# FOC_DRV8323.net
KiCad netlist of a schematic drawn in Altium Designer
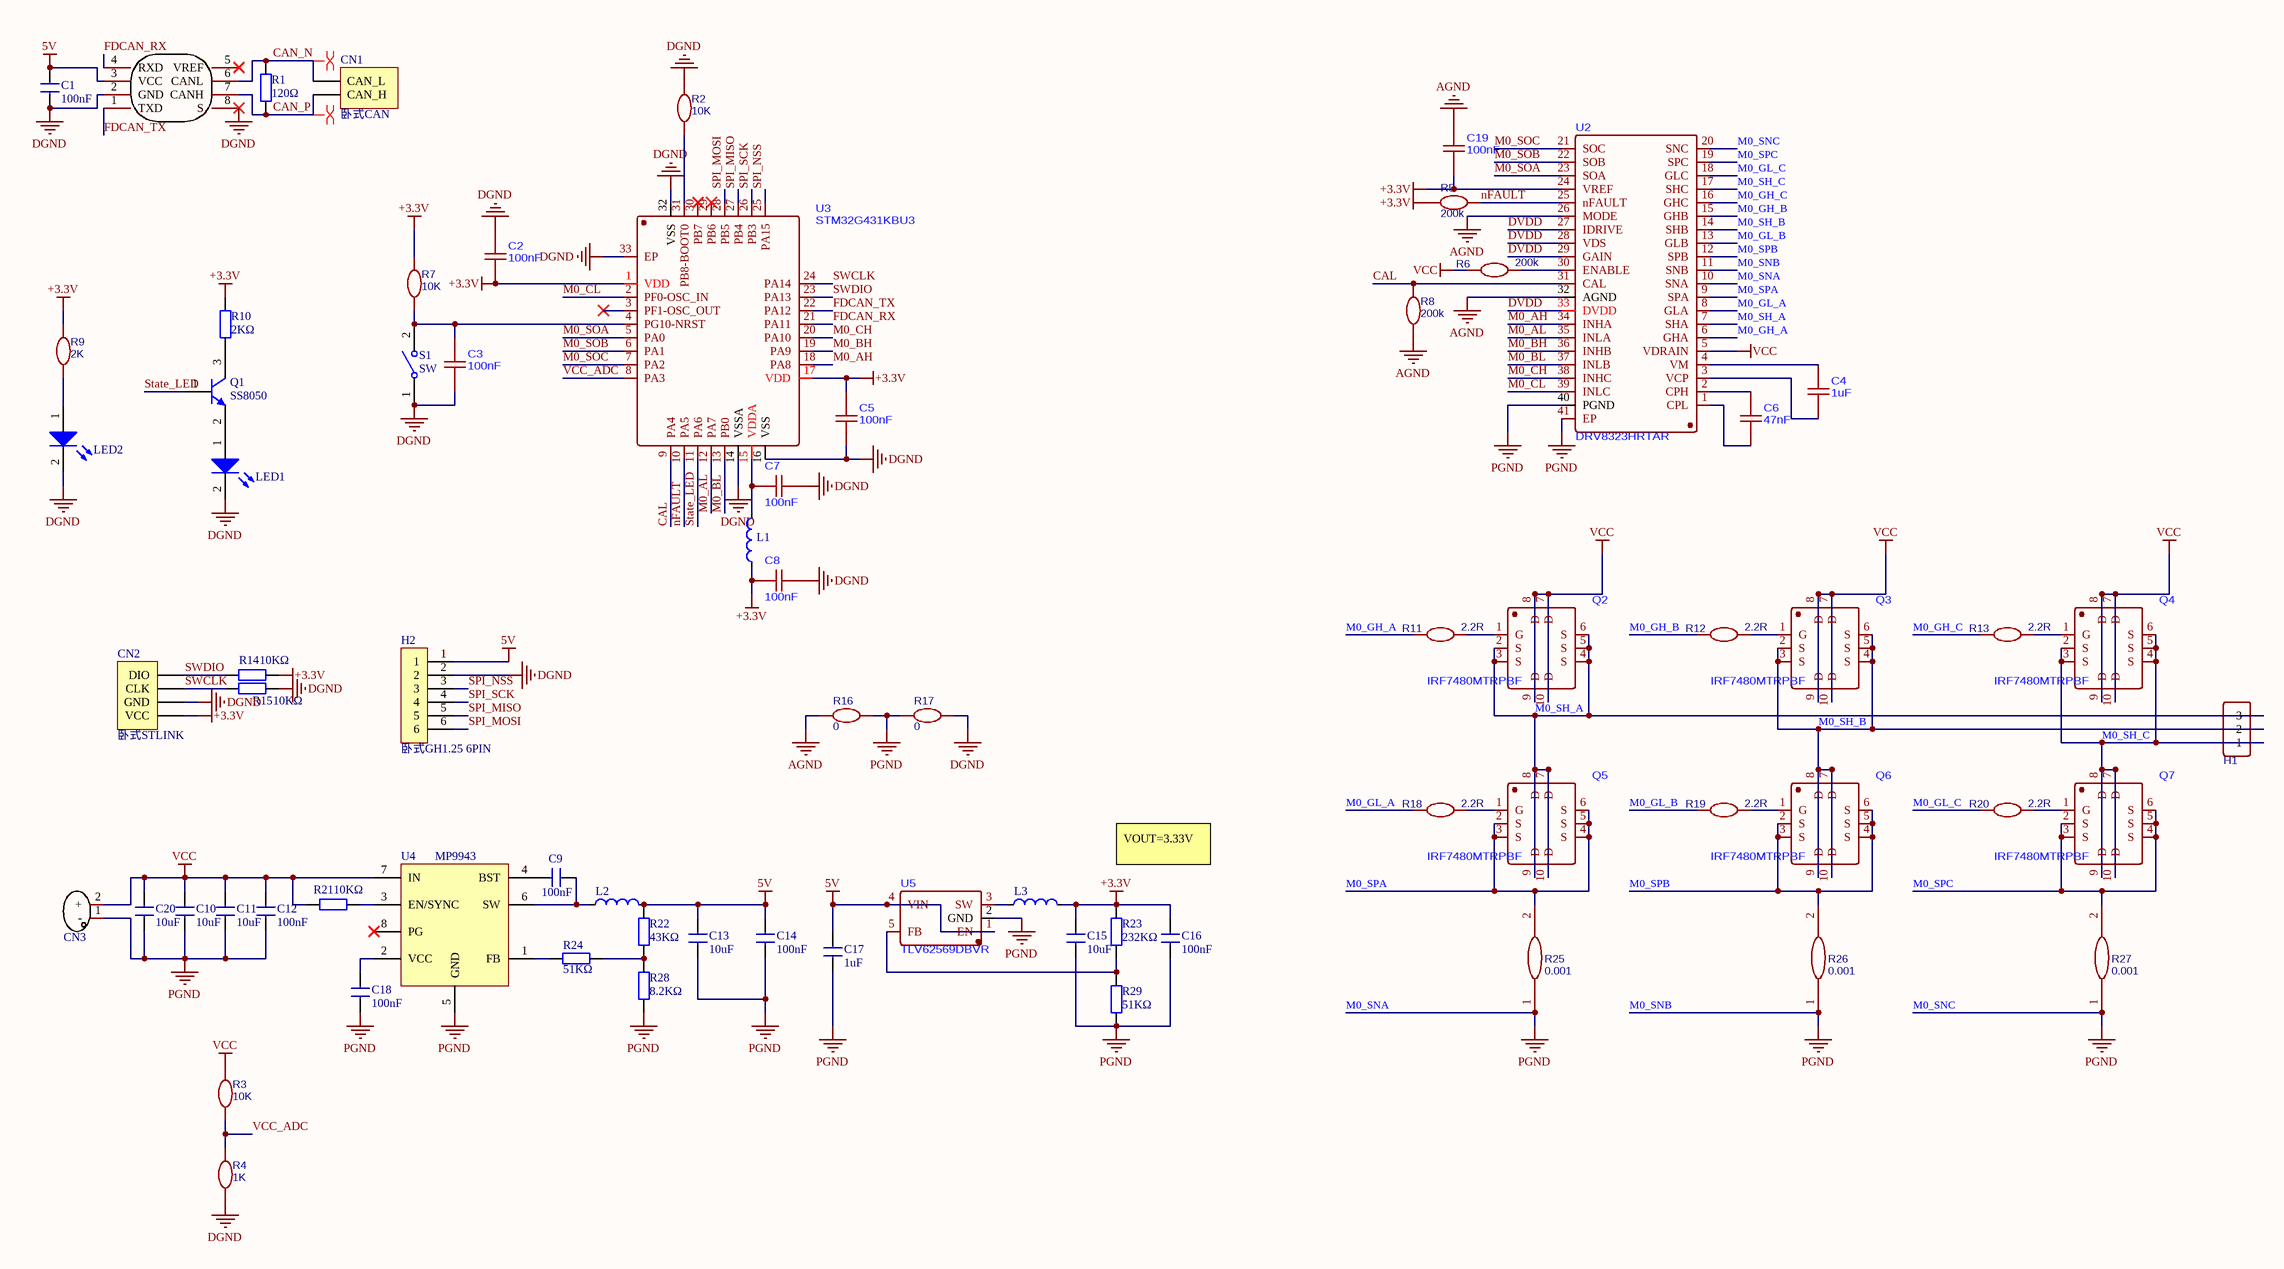
[diagram p0: FOC_DRV8323.SchDoc]

(export (version "E")
  (design (tool "Eeschema 10.0.6"))
  (components
    (comp (ref "C1")
      (value "100nF")
      (footprint "c0402")
      (description "贴片电容0402")
      (libsource (lib "Integrated_Library1") (part "0402贴片电容"))
    )
    (comp (ref "C2") (value "100nF") (footprint "c0402") (libsource (lib "PETO") (part "CC0201JRX7R9BB101")))
    (comp (ref "C3") (value "100nF") (footprint "c0402") (libsource (lib "PETO") (part "CC0201JRX7R9BB101")))
    (comp (ref "C4") (value "1uF") (footprint "c0402") (libsource (lib "PETO") (part "CC0201JRX7R9BB101")))
    (comp (ref "C5") (value "100nF") (footprint "c0402") (libsource (lib "PETO") (part "CC0201JRX7R9BB101")))
    (comp (ref "C6") (value "47nF") (footprint "c0402") (libsource (lib "PETO") (part "CC0201JRX7R9BB101")))
    (comp (ref "C7") (value "100nF") (footprint "c0402") (libsource (lib "PETO") (part "CC0201JRX7R9BB101")))
    (comp (ref "C8") (value "100nF") (footprint "c0402") (libsource (lib "PETO") (part "CC0201JRX7R9BB101")))
    (comp (ref "C9")
      (value "100nF")
      (footprint "c0402")
      (description "贴片电容0402")
      (libsource (lib "Integrated_Library1") (part "0402贴片电容"))
    )
    (comp (ref "C10")
      (value "10uF")
      (footprint "1210")
      (description "1210贴片电容")
      (libsource (lib "Integrated_Library1") (part "1210贴片电容"))
    )
    (comp (ref "C11")
      (value "10uF")
      (footprint "1210")
      (description "1210贴片电容")
      (libsource (lib "Integrated_Library1") (part "1210贴片电容"))
    )
    (comp (ref "C12")
      (value "100nF")
      (footprint "c0402")
      (description "贴片电容0402")
      (libsource (lib "Integrated_Library1") (part "0402贴片电容"))
    )
    (comp (ref "C13")
      (value "10uF")
      (footprint "1210")
      (description "1210贴片电容")
      (libsource (lib "Integrated_Library1") (part "1210贴片电容"))
    )
    (comp (ref "C14")
      (value "100nF")
      (footprint "c0402")
      (description "贴片电容0402")
      (libsource (lib "Integrated_Library1") (part "0402贴片电容"))
    )
    (comp (ref "C15")
      (value "10uF")
      (footprint "1210")
      (description "贴片电容0402")
      (libsource (lib "Integrated_Library1") (part "0402贴片电容"))
    )
    (comp (ref "C16")
      (value "100nF")
      (footprint "c0402")
      (description "贴片电容0402")
      (libsource (lib "Integrated_Library1") (part "0402贴片电容"))
    )
    (comp (ref "C17")
      (value "1uF")
      (footprint "c0402")
      (description "贴片电容0402")
      (libsource (lib "Integrated_Library1") (part "0402贴片电容"))
    )
    (comp (ref "C18")
      (value "100nF")
      (footprint "c0402")
      (description "贴片电容0402")
      (libsource (lib "Integrated_Library1") (part "0402贴片电容"))
    )
    (comp (ref "C19") (value "100nF") (footprint "c0402") (libsource (lib "PETO") (part "CC0201JRX7R9BB101")))
    (comp (ref "C20")
      (value "10uF")
      (footprint "1210")
      (description "1210贴片电容")
      (libsource (lib "Integrated_Library1") (part "1210贴片电容"))
    )
    (comp (ref "CN1")
      (value "卧式CAN")
      (footprint "GH1.25 2P 卧式")
      (fields (field (name "PUBLISHER") "Altium Limited"))
      (libsource (lib "Integrated_Library1") (part "卧式CAN"))
    )
    (comp (ref "CN2")
      (value "卧式STLINK")
      (footprint "CONN-SMD_4P-P1.25_GH1.25-4P")
      (libsource (lib "Integrated_Library1") (part "卧式STLINK"))
    )
    (comp (ref "CN3") (value "XT30_1") (footprint "XT30卧式焊盘") (libsource (lib "Schlib1") (part "XT30_1")))
    (comp (ref "H1")
      (value "MR30-M")
      (footprint "MR30")
      (fields (field (name "BOM_SUPPLIER PART") "C99873") (field (name "CONTRIBUTOR") "LCEDA_Lib"))
      (libsource (lib "altium-import") (part "root_2_MR30-M_"))
    )
    (comp (ref "H2")
      (value "卧式GH1.25 6PIN")
      (footprint "CONN-SMD_6P-P1.25_XYECONN_XY-GH1.25-6A61")
      (libsource (lib "En") (part "卧式GH1.25 6PIN"))
    )
    (comp (ref "L1")
      (value "1008屏蔽电感")
      (footprint "R0603")
      (libsource (lib "Integrated_Library1") (part "1008屏蔽电感"))
    )
    (comp (ref "L2")
      (value "1008屏蔽电感")
      (footprint "IND-SMD_L2.5-W2.0")
      (libsource (lib "Integrated_Library1") (part "1008屏蔽电感"))
    )
    (comp (ref "L3")
      (value "1008屏蔽电感")
      (footprint "IND-SMD_L2.5-W2.0")
      (libsource (lib "Integrated_Library1") (part "1008屏蔽电感"))
    )
    (comp (ref "LED1")
      (value "LED")
      (footprint "led0805")
      (description "0805贴片LED")
      (libsource (lib "Integrated_Library1") (part "0805贴片LED"))
    )
    (comp (ref "LED2")
      (value "LED")
      (footprint "led0805")
      (description "0805贴片LED")
      (libsource (lib "Integrated_Library1") (part "0805贴片LED"))
    )
    (comp (ref "Q1")
      (value "SS8050")
      (footprint "SOT-23-3_L2.9-W1.3-P1.90-LS2.4-BR")
      (description "三极管")
      (libsource (lib "Integrated_Library1") (part "2N2222"))
    )
    (comp (ref "Q2")
      (value "IRF7480MTRPBF")
      (footprint "TRS-SMD_IRF7480MTRPBF")
      (libsource (lib "FOC_DRV8301") (part "IRF7480MTRPBF"))
    )
    (comp (ref "Q3")
      (value "IRF7480MTRPBF")
      (footprint "TRS-SMD_IRF7480MTRPBF")
      (libsource (lib "FOC_DRV8301") (part "IRF7480MTRPBF"))
    )
    (comp (ref "Q4")
      (value "IRF7480MTRPBF")
      (footprint "TRS-SMD_IRF7480MTRPBF")
      (libsource (lib "FOC_DRV8301") (part "IRF7480MTRPBF"))
    )
    (comp (ref "Q5")
      (value "IRF7480MTRPBF")
      (footprint "TRS-SMD_IRF7480MTRPBF")
      (libsource (lib "FOC_DRV8301") (part "IRF7480MTRPBF"))
    )
    (comp (ref "Q6")
      (value "IRF7480MTRPBF")
      (footprint "TRS-SMD_IRF7480MTRPBF")
      (libsource (lib "FOC_DRV8301") (part "IRF7480MTRPBF"))
    )
    (comp (ref "Q7")
      (value "IRF7480MTRPBF")
      (footprint "TRS-SMD_IRF7480MTRPBF")
      (libsource (lib "FOC_DRV8301") (part "IRF7480MTRPBF"))
    )
    (comp (ref "R1")
      (value "120Ω")
      (footprint "R0402")
      (description "0402贴片电阻")
      (libsource (lib "") (part "0402贴片电阻_4"))
    )
    (comp (ref "R2")
      (value "10K")
      (footprint "R0402")
      (fields
        (field (name "BOM_MANUFACTURER PART") "0603WAJ022JT5E")
        (field (name "BOM_SUPPLIER PART") "C25226")
      )
      (libsource (lib "altium-import") (part "root_3_2.2R_"))
    )
    (comp (ref "R3")
      (value "10K")
      (footprint "R0402")
      (fields
        (field (name "BOM_MANUFACTURER PART") "0603WAJ022JT5E")
        (field (name "BOM_SUPPLIER PART") "C25226")
      )
      (libsource (lib "altium-import") (part "root_1_2.2R_"))
    )
    (comp (ref "R4")
      (value "1K")
      (footprint "R0402")
      (fields
        (field (name "BOM_MANUFACTURER PART") "0603WAJ022JT5E")
        (field (name "BOM_SUPPLIER PART") "C25226")
      )
      (libsource (lib "altium-import") (part "root_1_2.2R_"))
    )
    (comp (ref "R5")
      (value "200k")
      (footprint "R0402")
      (fields
        (field (name "BOM_MANUFACTURER PART") "0603WAJ022JT5E")
        (field (name "BOM_SUPPLIER PART") "C25226")
      )
      (libsource (lib "altium-import") (part "root_0_2.2R_"))
    )
    (comp (ref "R6")
      (value "200k")
      (footprint "R0402")
      (fields
        (field (name "BOM_MANUFACTURER PART") "0603WAJ022JT5E")
        (field (name "BOM_SUPPLIER PART") "C25226")
      )
      (libsource (lib "altium-import") (part "root_2_2.2R_"))
    )
    (comp (ref "R7")
      (value "10K")
      (footprint "R0402")
      (fields
        (field (name "BOM_MANUFACTURER PART") "0603WAJ022JT5E")
        (field (name "BOM_SUPPLIER PART") "C25226")
      )
      (libsource (lib "altium-import") (part "root_3_2.2R_"))
    )
    (comp (ref "R8")
      (value "200k")
      (footprint "R0402")
      (fields
        (field (name "BOM_MANUFACTURER PART") "0603WAJ022JT5E")
        (field (name "BOM_SUPPLIER PART") "C25226")
      )
      (libsource (lib "altium-import") (part "root_3_2.2R_"))
    )
    (comp (ref "R9")
      (value "2K")
      (footprint "R0402")
      (fields
        (field (name "BOM_MANUFACTURER PART") "0603WAJ022JT5E")
        (field (name "BOM_SUPPLIER PART") "C25226")
      )
      (libsource (lib "altium-import") (part "root_3_2.2R_"))
    )
    (comp (ref "R10")
      (value "2KΩ")
      (footprint "R0402")
      (description "0402贴片电阻")
      (libsource (lib "") (part "0402贴片电阻_4"))
    )
    (comp (ref "R11")
      (value "2.2R")
      (footprint "R0402")
      (fields
        (field (name "BOM_MANUFACTURER PART") "0603WAJ022JT5E")
        (field (name "BOM_SUPPLIER PART") "C25226")
      )
      (libsource (lib "altium-import") (part "root_2_2.2R_"))
    )
    (comp (ref "R12")
      (value "2.2R")
      (footprint "R0402")
      (fields
        (field (name "BOM_MANUFACTURER PART") "0603WAJ022JT5E")
        (field (name "BOM_SUPPLIER PART") "C25226")
      )
      (libsource (lib "altium-import") (part "root_2_2.2R_"))
    )
    (comp (ref "R13")
      (value "2.2R")
      (footprint "R0402")
      (fields
        (field (name "BOM_MANUFACTURER PART") "0603WAJ022JT5E")
        (field (name "BOM_SUPPLIER PART") "C25226")
      )
      (libsource (lib "altium-import") (part "root_2_2.2R_"))
    )
    (comp (ref "R14")
      (value "10KΩ")
      (footprint "R0402")
      (description "0402贴片电阻")
      (libsource (lib "Integrated_Library1") (part "0402贴片电阻"))
    )
    (comp (ref "R15")
      (value "10KΩ")
      (footprint "R0402")
      (description "0402贴片电阻")
      (libsource (lib "") (part "0402贴片电阻_3"))
    )
    (comp (ref "R16")
      (value "0")
      (footprint "R0402")
      (fields
        (field (name "BOM_MANUFACTURER PART") "0603WAJ022JT5E")
        (field (name "BOM_SUPPLIER PART") "C25226")
      )
      (libsource (lib "altium-import") (part "root_0_2.2R_"))
    )
    (comp (ref "R17")
      (value "0")
      (footprint "R0402")
      (fields
        (field (name "BOM_MANUFACTURER PART") "0603WAJ022JT5E")
        (field (name "BOM_SUPPLIER PART") "C25226")
      )
      (libsource (lib "altium-import") (part "root_0_2.2R_"))
    )
    (comp (ref "R18")
      (value "2.2R")
      (footprint "R0402")
      (fields
        (field (name "BOM_MANUFACTURER PART") "0603WAJ022JT5E")
        (field (name "BOM_SUPPLIER PART") "C25226")
      )
      (libsource (lib "altium-import") (part "root_2_2.2R_"))
    )
    (comp (ref "R19")
      (value "2.2R")
      (footprint "R0402")
      (fields
        (field (name "BOM_MANUFACTURER PART") "0603WAJ022JT5E")
        (field (name "BOM_SUPPLIER PART") "C25226")
      )
      (libsource (lib "altium-import") (part "root_2_2.2R_"))
    )
    (comp (ref "R20")
      (value "2.2R")
      (footprint "R0402")
      (fields
        (field (name "BOM_MANUFACTURER PART") "0603WAJ022JT5E")
        (field (name "BOM_SUPPLIER PART") "C25226")
      )
      (libsource (lib "altium-import") (part "root_2_2.2R_"))
    )
    (comp (ref "R21")
      (value "10KΩ")
      (footprint "R0402")
      (description "0402贴片电阻")
      (libsource (lib "") (part "0402贴片电阻_1"))
    )
    (comp (ref "R22")
      (value "43KΩ")
      (footprint "R0402")
      (description "0402贴片电阻")
      (libsource (lib "") (part "0402贴片电阻_2"))
    )
    (comp (ref "R23")
      (value "232KΩ")
      (footprint "R0402")
      (description "0402贴片电阻")
      (libsource (lib "") (part "0402贴片电阻_2"))
    )
    (comp (ref "R24")
      (value "51KΩ")
      (footprint "R0402")
      (description "0402贴片电阻")
      (libsource (lib "") (part "0402贴片电阻_1"))
    )
    (comp (ref "R25")
      (value "0.001")
      (footprint "R0612")
      (fields
        (field (name "BOM_SUPPLIER PART") "C2681067")
        (field (name "BOM_MANUFACTURER PART") "LR2512-23R0005J4")
        (field (name "CONTRIBUTOR") "LCSC")
      )
      (libsource (lib "altium-import") (part "root_1_0.0005_"))
    )
    (comp (ref "R26")
      (value "0.001")
      (footprint "R0612")
      (fields
        (field (name "BOM_SUPPLIER PART") "C2681067")
        (field (name "BOM_MANUFACTURER PART") "LR2512-23R0005J4")
        (field (name "CONTRIBUTOR") "LCSC")
      )
      (libsource (lib "altium-import") (part "root_1_0.0005_"))
    )
    (comp (ref "R27")
      (value "0.001")
      (footprint "R0612")
      (fields
        (field (name "BOM_SUPPLIER PART") "C2681067")
        (field (name "BOM_MANUFACTURER PART") "LR2512-23R0005J4")
        (field (name "CONTRIBUTOR") "LCSC")
      )
      (libsource (lib "altium-import") (part "root_1_0.0005_"))
    )
    (comp (ref "R28")
      (value "8.2KΩ")
      (footprint "R0402")
      (description "0402贴片电阻")
      (libsource (lib "") (part "0402贴片电阻_2"))
    )
    (comp (ref "R29")
      (value "51KΩ")
      (footprint "R0402")
      (description "0402贴片电阻")
      (libsource (lib "") (part "0402贴片电阻_2"))
    )
    (comp (ref "S1")
      (value "SW")
      (footprint "KEY_SMD")
      (description "开关")
      (libsource (lib "Integrated_Library1") (part "SW"))
    )
    (comp (ref "U1")
      (value "SN65HVD1050DR")
      (footprint "SOIC-8_L4.9-W3.9-P1.27-LS6.0-BL")
      (description "CAN芯片")
      (fields (field (name "MANUFACTURER") "TI(德州仪器)"))
      (libsource (lib "Integrated_Library1") (part "SN65HVD1050DR"))
    )
    (comp (ref "U2")
      (value "DRV8323HRTAR")
      (footprint "QFN-40_L6.0-W6.0-P0.50-BL-EP4.5")
      (libsource (lib "FOC_DRV8323") (part "DRV8323HRTAR"))
    )
    (comp (ref "U3")
      (value "STM32G431KBU3")
      (footprint "UFQFPN-32_L5.0-W5.0-P0.50-BL-EP3.5")
      (libsource (lib "FOC_DRV8323") (part "STM32G431KBU3"))
    )
    (comp (ref "U4")
      (value "MP9943")
      (footprint "QFN-8 3x3")
      (libsource (lib "Integrated_Library1") (part "MP9943"))
    )
    (comp (ref "U5")
      (value "TLV62569DBVR")
      (footprint "SOT-23-5_L3.0-W1.7-P0.95-LS2.8-BR")
      (libsource (lib "FOC_DRV8323") (part "TLV62569DBVR"))
    )
  )
  (nets
    (net (code "1") (name "+3.3V") (class "Default")
      (node (ref "C15") (pin "2") (pinfunction "2_2") (pintype "passive"))
      (node (ref "C16") (pin "2") (pinfunction "2_2") (pintype "passive"))
      (node (ref "C19") (pin "1") (pinfunction "1_1") (pintype "passive"))
      (node (ref "C2") (pin "2") (pinfunction "2_2") (pintype "passive"))
      (node (ref "C5") (pin "2") (pinfunction "2_2") (pintype "passive"))
      (node (ref "C8") (pin "2") (pinfunction "2_2") (pintype "passive"))
      (node (ref "CN2") (pin "1") (pinfunction "VCC_1") (pintype "passive"))
      (node (ref "L1") (pin "1") (pinfunction "1_1") (pintype "passive"))
      (node (ref "L3") (pin "2") (pinfunction "2_2") (pintype "passive"))
      (node (ref "R10") (pin "2") (pinfunction "2_2") (pintype "passive"))
      (node (ref "R14") (pin "1") (pinfunction "1_1") (pintype "passive"))
      (node (ref "R23") (pin "2") (pinfunction "2_2") (pintype "passive"))
      (node (ref "R5") (pin "1") (pinfunction "1_1") (pintype "passive"))
      (node (ref "R7") (pin "1") (pinfunction "1_1") (pintype "passive"))
      (node (ref "R9") (pin "1") (pinfunction "1_1") (pintype "passive"))
      (node (ref "U2") (pin "24") (pinfunction "VREF_24") (pintype "passive"))
      (node (ref "U3") (pin "1") (pinfunction "VDD_1") (pintype "passive"))
      (node (ref "U3") (pin "17") (pinfunction "VDD_17") (pintype "passive"))
    )
    (net (code "2") (name "/CAL") (class "Default")
      (node (ref "R8") (pin "1") (pinfunction "1_1") (pintype "passive"))
      (node (ref "U2") (pin "31") (pinfunction "CAL_31") (pintype "passive"))
      (node (ref "U3") (pin "9") (pinfunction "PA4_9") (pintype "passive"))
    )
    (net (code "3") (name "/CAN_N") (class "Default")
      (node (ref "CN1") (pin "2") (pinfunction "CAN_L_2") (pintype "passive"))
      (node (ref "R1") (pin "2") (pinfunction "2_2") (pintype "passive"))
      (node (ref "U1") (pin "6") (pinfunction "CANL_6") (pintype "passive"))
    )
    (net (code "4") (name "/CAN_P") (class "Default")
      (node (ref "CN1") (pin "1") (pinfunction "CAN_H_1") (pintype "passive"))
      (node (ref "R1") (pin "1") (pinfunction "1_1") (pintype "passive"))
      (node (ref "U1") (pin "7") (pinfunction "CANH_7") (pintype "passive"))
    )
    (net (code "5") (name "/DVDD") (class "Default")
      (node (ref "U2") (pin "27") (pinfunction "IDRIVE_27") (pintype "passive"))
      (node (ref "U2") (pin "28") (pinfunction "VDS_28") (pintype "passive"))
      (node (ref "U2") (pin "29") (pinfunction "GAIN_29") (pintype "passive"))
      (node (ref "U2") (pin "33") (pinfunction "DVDD_33") (pintype "passive"))
    )
    (net (code "6") (name "/FDCAN_RX") (class "Default")
      (node (ref "U1") (pin "4") (pinfunction "RXD_4") (pintype "passive"))
      (node (ref "U3") (pin "21") (pinfunction "PA11_21") (pintype "passive"))
    )
    (net (code "7") (name "/FDCAN_TX") (class "Default")
      (node (ref "U1") (pin "1") (pinfunction "TXD_1") (pintype "passive"))
      (node (ref "U3") (pin "22") (pinfunction "PA12_22") (pintype "passive"))
    )
    (net (code "8") (name "/M0_AH") (class "Default")
      (node (ref "U2") (pin "34") (pinfunction "INHA_34") (pintype "passive"))
      (node (ref "U3") (pin "18") (pinfunction "PA8_18") (pintype "passive"))
    )
    (net (code "9") (name "/M0_AL") (class "Default")
      (node (ref "U2") (pin "35") (pinfunction "INLA_35") (pintype "passive"))
      (node (ref "U3") (pin "12") (pinfunction "PA7_12") (pintype "passive"))
    )
    (net (code "10") (name "/M0_BH") (class "Default")
      (node (ref "U2") (pin "36") (pinfunction "INHB_36") (pintype "passive"))
      (node (ref "U3") (pin "19") (pinfunction "PA9_19") (pintype "passive"))
    )
    (net (code "11") (name "/M0_BL") (class "Default")
      (node (ref "U2") (pin "37") (pinfunction "INLB_37") (pintype "passive"))
      (node (ref "U3") (pin "13") (pinfunction "PB0_13") (pintype "passive"))
    )
    (net (code "12") (name "/M0_CH") (class "Default")
      (node (ref "U2") (pin "38") (pinfunction "INHC_38") (pintype "passive"))
      (node (ref "U3") (pin "20") (pinfunction "PA10_20") (pintype "passive"))
    )
    (net (code "13") (name "/M0_CL") (class "Default")
      (node (ref "U2") (pin "39") (pinfunction "INLC_39") (pintype "passive"))
      (node (ref "U3") (pin "2") (pinfunction "PF0-OSC_IN_2") (pintype "passive"))
    )
    (net (code "14") (name "/M0_GH_A") (class "Default")
      (node (ref "R11") (pin "2") (pinfunction "2_2") (pintype "passive"))
      (node (ref "U2") (pin "6") (pinfunction "GHA_6") (pintype "passive"))
    )
    (net (code "15") (name "/M0_GH_B") (class "Default")
      (node (ref "R12") (pin "2") (pinfunction "2_2") (pintype "passive"))
      (node (ref "U2") (pin "15") (pinfunction "GHB_15") (pintype "passive"))
    )
    (net (code "16") (name "/M0_GH_C") (class "Default")
      (node (ref "R13") (pin "2") (pinfunction "2_2") (pintype "passive"))
      (node (ref "U2") (pin "16") (pinfunction "GHC_16") (pintype "passive"))
    )
    (net (code "17") (name "/M0_GL_A") (class "Default")
      (node (ref "R18") (pin "2") (pinfunction "2_2") (pintype "passive"))
      (node (ref "U2") (pin "8") (pinfunction "GLA_8") (pintype "passive"))
    )
    (net (code "18") (name "/M0_GL_B") (class "Default")
      (node (ref "R19") (pin "2") (pinfunction "2_2") (pintype "passive"))
      (node (ref "U2") (pin "13") (pinfunction "GLB_13") (pintype "passive"))
    )
    (net (code "19") (name "/M0_GL_C") (class "Default")
      (node (ref "R20") (pin "2") (pinfunction "2_2") (pintype "passive"))
      (node (ref "U2") (pin "18") (pinfunction "GLC_18") (pintype "passive"))
    )
    (net (code "20") (name "/M0_SH_A") (class "Default")
      (node (ref "H1") (pin "3") (pinfunction "3_3") (pintype "passive"))
      (node (ref "Q2") (pin "2") (pinfunction "S_2") (pintype "passive"))
      (node (ref "Q2") (pin "3") (pinfunction "S_3") (pintype "passive"))
      (node (ref "Q2") (pin "4") (pinfunction "S_4") (pintype "passive"))
      (node (ref "Q2") (pin "5") (pinfunction "S_5") (pintype "passive"))
      (node (ref "Q2") (pin "6") (pinfunction "S_6") (pintype "passive"))
      (node (ref "Q5") (pin "10") (pinfunction "D_10") (pintype "passive"))
      (node (ref "Q5") (pin "7") (pinfunction "D_7") (pintype "passive"))
      (node (ref "Q5") (pin "8") (pinfunction "D_8") (pintype "passive"))
      (node (ref "Q5") (pin "9") (pinfunction "D_9") (pintype "passive"))
      (node (ref "U2") (pin "7") (pinfunction "SHA_7") (pintype "passive"))
    )
    (net (code "21") (name "/M0_SH_B") (class "Default")
      (node (ref "H1") (pin "2") (pinfunction "2_2") (pintype "passive"))
      (node (ref "Q3") (pin "2") (pinfunction "S_2") (pintype "passive"))
      (node (ref "Q3") (pin "3") (pinfunction "S_3") (pintype "passive"))
      (node (ref "Q3") (pin "4") (pinfunction "S_4") (pintype "passive"))
      (node (ref "Q3") (pin "5") (pinfunction "S_5") (pintype "passive"))
      (node (ref "Q3") (pin "6") (pinfunction "S_6") (pintype "passive"))
      (node (ref "Q6") (pin "10") (pinfunction "D_10") (pintype "passive"))
      (node (ref "Q6") (pin "7") (pinfunction "D_7") (pintype "passive"))
      (node (ref "Q6") (pin "8") (pinfunction "D_8") (pintype "passive"))
      (node (ref "Q6") (pin "9") (pinfunction "D_9") (pintype "passive"))
      (node (ref "U2") (pin "14") (pinfunction "SHB_14") (pintype "passive"))
    )
    (net (code "22") (name "/M0_SH_C") (class "Default")
      (node (ref "H1") (pin "1") (pinfunction "1_1") (pintype "passive"))
      (node (ref "Q4") (pin "2") (pinfunction "S_2") (pintype "passive"))
      (node (ref "Q4") (pin "3") (pinfunction "S_3") (pintype "passive"))
      (node (ref "Q4") (pin "4") (pinfunction "S_4") (pintype "passive"))
      (node (ref "Q4") (pin "5") (pinfunction "S_5") (pintype "passive"))
      (node (ref "Q4") (pin "6") (pinfunction "S_6") (pintype "passive"))
      (node (ref "Q7") (pin "10") (pinfunction "D_10") (pintype "passive"))
      (node (ref "Q7") (pin "7") (pinfunction "D_7") (pintype "passive"))
      (node (ref "Q7") (pin "8") (pinfunction "D_8") (pintype "passive"))
      (node (ref "Q7") (pin "9") (pinfunction "D_9") (pintype "passive"))
      (node (ref "U2") (pin "17") (pinfunction "SHC_17") (pintype "passive"))
    )
    (net (code "23") (name "/M0_SOA") (class "Default")
      (node (ref "U2") (pin "23") (pinfunction "SOA_23") (pintype "passive"))
      (node (ref "U3") (pin "5") (pinfunction "PA0_5") (pintype "passive"))
    )
    (net (code "24") (name "/M0_SOB") (class "Default")
      (node (ref "U2") (pin "22") (pinfunction "SOB_22") (pintype "passive"))
      (node (ref "U3") (pin "6") (pinfunction "PA1_6") (pintype "passive"))
    )
    (net (code "25") (name "/M0_SOC") (class "Default")
      (node (ref "U2") (pin "21") (pinfunction "SOC_21") (pintype "passive"))
      (node (ref "U3") (pin "7") (pinfunction "PA2_7") (pintype "passive"))
    )
    (net (code "26") (name "/M0_SPA") (class "Default")
      (node (ref "Q5") (pin "2") (pinfunction "S_2") (pintype "passive"))
      (node (ref "Q5") (pin "3") (pinfunction "S_3") (pintype "passive"))
      (node (ref "Q5") (pin "4") (pinfunction "S_4") (pintype "passive"))
      (node (ref "Q5") (pin "5") (pinfunction "S_5") (pintype "passive"))
      (node (ref "Q5") (pin "6") (pinfunction "S_6") (pintype "passive"))
      (node (ref "R25") (pin "2") (pinfunction "2_2") (pintype "passive"))
      (node (ref "U2") (pin "9") (pinfunction "SPA_9") (pintype "passive"))
    )
    (net (code "27") (name "/M0_SPB") (class "Default")
      (node (ref "Q6") (pin "2") (pinfunction "S_2") (pintype "passive"))
      (node (ref "Q6") (pin "3") (pinfunction "S_3") (pintype "passive"))
      (node (ref "Q6") (pin "4") (pinfunction "S_4") (pintype "passive"))
      (node (ref "Q6") (pin "5") (pinfunction "S_5") (pintype "passive"))
      (node (ref "Q6") (pin "6") (pinfunction "S_6") (pintype "passive"))
      (node (ref "R26") (pin "2") (pinfunction "2_2") (pintype "passive"))
      (node (ref "U2") (pin "12") (pinfunction "SPB_12") (pintype "passive"))
    )
    (net (code "28") (name "/M0_SPC") (class "Default")
      (node (ref "Q7") (pin "2") (pinfunction "S_2") (pintype "passive"))
      (node (ref "Q7") (pin "3") (pinfunction "S_3") (pintype "passive"))
      (node (ref "Q7") (pin "4") (pinfunction "S_4") (pintype "passive"))
      (node (ref "Q7") (pin "5") (pinfunction "S_5") (pintype "passive"))
      (node (ref "Q7") (pin "6") (pinfunction "S_6") (pintype "passive"))
      (node (ref "R27") (pin "2") (pinfunction "2_2") (pintype "passive"))
      (node (ref "U2") (pin "19") (pinfunction "SPC_19") (pintype "passive"))
    )
    (net (code "29") (name "/SPI_MISO") (class "Default")
      (node (ref "H2") (pin "5") (pinfunction "5_5") (pintype "passive"))
      (node (ref "U3") (pin "27") (pinfunction "PB4_27") (pintype "passive"))
    )
    (net (code "30") (name "/SPI_MOSI") (class "Default")
      (node (ref "H2") (pin "6") (pinfunction "6_6") (pintype "passive"))
      (node (ref "U3") (pin "28") (pinfunction "PB5_28") (pintype "passive"))
    )
    (net (code "31") (name "/SPI_NSS") (class "Default")
      (node (ref "H2") (pin "3") (pinfunction "3_3") (pintype "passive"))
      (node (ref "U3") (pin "25") (pinfunction "PA15_25") (pintype "passive"))
    )
    (net (code "32") (name "/SPI_SCK") (class "Default")
      (node (ref "H2") (pin "4") (pinfunction "4_4") (pintype "passive"))
      (node (ref "U3") (pin "26") (pinfunction "PB3_26") (pintype "passive"))
    )
    (net (code "33") (name "/SWCLK") (class "Default")
      (node (ref "CN2") (pin "3") (pinfunction "CLK_3") (pintype "passive"))
      (node (ref "R15") (pin "1") (pinfunction "1_1") (pintype "passive"))
      (node (ref "U3") (pin "24") (pinfunction "PA14_24") (pintype "passive"))
    )
    (net (code "34") (name "/SWDIO") (class "Default")
      (node (ref "CN2") (pin "4") (pinfunction "DIO_4") (pintype "passive"))
      (node (ref "R14") (pin "2") (pinfunction "2_2") (pintype "passive"))
      (node (ref "U3") (pin "23") (pinfunction "PA13_23") (pintype "passive"))
    )
    (net (code "35") (name "/State_LED") (class "Default")
      (node (ref "Q1") (pin "1") (pinfunction "B_1") (pintype "passive"))
      (node (ref "U3") (pin "11") (pinfunction "PA6_11") (pintype "passive"))
    )
    (net (code "36") (name "/VCC_ADC") (class "Default")
      (node (ref "R3") (pin "1") (pinfunction "1_1") (pintype "passive"))
      (node (ref "R4") (pin "2") (pinfunction "2_2") (pintype "passive"))
      (node (ref "U3") (pin "8") (pinfunction "PA3_8") (pintype "passive"))
    )
    (net (code "37") (name "/nFAULT") (class "Default")
      (node (ref "R5") (pin "2") (pinfunction "2_2") (pintype "passive"))
      (node (ref "U2") (pin "25") (pinfunction "nFAULT_25") (pintype "passive"))
      (node (ref "U3") (pin "10") (pinfunction "PA5_10") (pintype "passive"))
    )
    (net (code "38") (name "5V") (class "Default")
      (node (ref "C1") (pin "2") (pinfunction "2_2") (pintype "passive"))
      (node (ref "C13") (pin "2") (pinfunction "2_2") (pintype "passive"))
      (node (ref "C14") (pin "2") (pinfunction "2_2") (pintype "passive"))
      (node (ref "C17") (pin "2") (pinfunction "2_2") (pintype "passive"))
      (node (ref "H2") (pin "1") (pinfunction "1_1") (pintype "passive"))
      (node (ref "L2") (pin "2") (pinfunction "2_2") (pintype "passive"))
      (node (ref "R22") (pin "2") (pinfunction "2_2") (pintype "passive"))
      (node (ref "U1") (pin "3") (pinfunction "VCC_3") (pintype "passive"))
      (node (ref "U5") (pin "1") (pinfunction "EN_1") (pintype "passive"))
      (node (ref "U5") (pin "4") (pinfunction "VIN_4") (pintype "passive"))
    )
    (net (code "39") (name "AGND") (class "Default")
      (node (ref "C19") (pin "2") (pinfunction "2_2") (pintype "passive"))
      (node (ref "R16") (pin "1") (pinfunction "1_1") (pintype "passive"))
      (node (ref "R8") (pin "2") (pinfunction "2_2") (pintype "passive"))
      (node (ref "U2") (pin "26") (pinfunction "MODE_26") (pintype "passive"))
      (node (ref "U2") (pin "32") (pinfunction "AGND_32") (pintype "passive"))
    )
    (net (code "40") (name "DGND") (class "Default")
      (node (ref "C1") (pin "1") (pinfunction "1_1") (pintype "passive"))
      (node (ref "C2") (pin "1") (pinfunction "1_1") (pintype "passive"))
      (node (ref "C3") (pin "1") (pinfunction "1_1") (pintype "passive"))
      (node (ref "C5") (pin "1") (pinfunction "1_1") (pintype "passive"))
      (node (ref "C7") (pin "1") (pinfunction "1_1") (pintype "passive"))
      (node (ref "C8") (pin "1") (pinfunction "1_1") (pintype "passive"))
      (node (ref "CN2") (pin "2") (pinfunction "GND_2") (pintype "passive"))
      (node (ref "H2") (pin "2") (pinfunction "2_2") (pintype "passive"))
      (node (ref "LED1") (pin "2") (pinfunction "K_2") (pintype "passive"))
      (node (ref "LED2") (pin "2") (pinfunction "K_2") (pintype "passive"))
      (node (ref "R15") (pin "2") (pinfunction "2_2") (pintype "passive"))
      (node (ref "R17") (pin "2") (pinfunction "2_2") (pintype "passive"))
      (node (ref "R2") (pin "1") (pinfunction "1_1") (pintype "passive"))
      (node (ref "R4") (pin "1") (pinfunction "1_1") (pintype "passive"))
      (node (ref "S1") (pin "1") (pinfunction "COMMON_1") (pintype "passive"))
      (node (ref "U1") (pin "2") (pinfunction "GND_2") (pintype "passive"))
      (node (ref "U1") (pin "8") (pinfunction "S_8") (pintype "passive"))
      (node (ref "U3") (pin "14") (pinfunction "VSSA_14") (pintype "passive"))
      (node (ref "U3") (pin "16") (pinfunction "VSS_16") (pintype "passive"))
      (node (ref "U3") (pin "32") (pinfunction "VSS_32") (pintype "passive"))
      (node (ref "U3") (pin "33") (pinfunction "EP_33") (pintype "passive"))
    )
    (net (code "41") (name "Net-(LED1-A)") (class "Default")
      (node (ref "LED1") (pin "1") (pinfunction "A_1") (pintype "passive"))
      (node (ref "Q1") (pin "2") (pinfunction "E_2") (pintype "passive"))
    )
    (net (code "42") (name "Net-(LED2-A)") (class "Default")
      (node (ref "LED2") (pin "1") (pinfunction "A_1") (pintype "passive"))
      (node (ref "R9") (pin "2") (pinfunction "2_2") (pintype "passive"))
    )
    (net (code "43") (name "Net-(Q1-C)") (class "Default")
      (node (ref "Q1") (pin "3") (pinfunction "C_3") (pintype "passive"))
      (node (ref "R10") (pin "1") (pinfunction "1_1") (pintype "passive"))
    )
    (net (code "44") (name "Net-(Q2-G)") (class "Default")
      (node (ref "Q2") (pin "1") (pinfunction "G_1") (pintype "passive"))
      (node (ref "R11") (pin "1") (pinfunction "1_1") (pintype "passive"))
    )
    (net (code "45") (name "Net-(Q3-G)") (class "Default")
      (node (ref "Q3") (pin "1") (pinfunction "G_1") (pintype "passive"))
      (node (ref "R12") (pin "1") (pinfunction "1_1") (pintype "passive"))
    )
    (net (code "46") (name "Net-(Q4-G)") (class "Default")
      (node (ref "Q4") (pin "1") (pinfunction "G_1") (pintype "passive"))
      (node (ref "R13") (pin "1") (pinfunction "1_1") (pintype "passive"))
    )
    (net (code "47") (name "Net-(Q5-G)") (class "Default")
      (node (ref "Q5") (pin "1") (pinfunction "G_1") (pintype "passive"))
      (node (ref "R18") (pin "1") (pinfunction "1_1") (pintype "passive"))
    )
    (net (code "48") (name "Net-(Q6-G)") (class "Default")
      (node (ref "Q6") (pin "1") (pinfunction "G_1") (pintype "passive"))
      (node (ref "R19") (pin "1") (pinfunction "1_1") (pintype "passive"))
    )
    (net (code "49") (name "Net-(Q7-G)") (class "Default")
      (node (ref "Q7") (pin "1") (pinfunction "G_1") (pintype "passive"))
      (node (ref "R20") (pin "1") (pinfunction "1_1") (pintype "passive"))
    )
    (net (code "50") (name "Net-(R22-Pad1)") (class "Default")
      (node (ref "R22") (pin "1") (pinfunction "1_1") (pintype "passive"))
      (node (ref "R24") (pin "2") (pinfunction "2_2") (pintype "passive"))
      (node (ref "R28") (pin "2") (pinfunction "2_2") (pintype "passive"))
    )
    (net (code "51") (name "Net-(S1-NO)") (class "Default")
      (node (ref "C3") (pin "2") (pinfunction "2_2") (pintype "passive"))
      (node (ref "R7") (pin "2") (pinfunction "2_2") (pintype "passive"))
      (node (ref "S1") (pin "2") (pinfunction "NO_2") (pintype "passive"))
      (node (ref "U3") (pin "4") (pinfunction "PG10-NRST_4") (pintype "passive"))
    )
    (net (code "52") (name "Net-(U2-CPH)") (class "Default")
      (node (ref "C6") (pin "2") (pinfunction "2_2") (pintype "passive"))
      (node (ref "U2") (pin "2") (pinfunction "CPH_2") (pintype "passive"))
    )
    (net (code "53") (name "Net-(U2-CPL)") (class "Default")
      (node (ref "C6") (pin "1") (pinfunction "1_1") (pintype "passive"))
      (node (ref "U2") (pin "1") (pinfunction "CPL_1") (pintype "passive"))
    )
    (net (code "54") (name "Net-(U2-ENABLE)") (class "Default")
      (node (ref "R6") (pin "1") (pinfunction "1_1") (pintype "passive"))
      (node (ref "U2") (pin "30") (pinfunction "ENABLE_30") (pintype "passive"))
    )
    (net (code "55") (name "Net-(U2-VCP)") (class "Default")
      (node (ref "C4") (pin "1") (pinfunction "1_1") (pintype "passive"))
      (node (ref "U2") (pin "3") (pinfunction "VCP_3") (pintype "passive"))
    )
    (net (code "56") (name "Net-(U2-VM)") (class "Default")
      (node (ref "C4") (pin "2") (pinfunction "2_2") (pintype "passive"))
      (node (ref "U2") (pin "4") (pinfunction "VM_4") (pintype "passive"))
    )
    (net (code "57") (name "Net-(U3-PB8-BOOT0)") (class "Default")
      (node (ref "R2") (pin "2") (pinfunction "2_2") (pintype "passive"))
      (node (ref "U3") (pin "31") (pinfunction "PB8-BOOT0_31") (pintype "passive"))
    )
    (net (code "58") (name "Net-(U3-VDDA)") (class "Default")
      (node (ref "C7") (pin "2") (pinfunction "2_2") (pintype "passive"))
      (node (ref "L1") (pin "2") (pinfunction "2_2") (pintype "passive"))
      (node (ref "U3") (pin "15") (pinfunction "VDDA_15") (pintype "passive"))
    )
    (net (code "59") (name "Net-(U4-BST)") (class "Default")
      (node (ref "C9") (pin "1") (pinfunction "1_1") (pintype "passive"))
      (node (ref "U4") (pin "4") (pinfunction "BST_4") (pintype "passive"))
    )
    (net (code "60") (name "Net-(U4-EN{slash}SYNC)") (class "Default")
      (node (ref "R21") (pin "2") (pinfunction "2_2") (pintype "passive"))
      (node (ref "U4") (pin "3") (pinfunction "EN/SYNC_3") (pintype "passive"))
    )
    (net (code "61") (name "Net-(U4-FB)") (class "Default")
      (node (ref "R24") (pin "1") (pinfunction "1_1") (pintype "passive"))
      (node (ref "U4") (pin "1") (pinfunction "FB_1") (pintype "passive"))
    )
    (net (code "62") (name "Net-(U4-SW)") (class "Default")
      (node (ref "C9") (pin "2") (pinfunction "2_2") (pintype "passive"))
      (node (ref "L2") (pin "1") (pinfunction "1_1") (pintype "passive"))
      (node (ref "U4") (pin "6") (pinfunction "SW_6") (pintype "passive"))
    )
    (net (code "63") (name "Net-(U4-VCC)") (class "Default")
      (node (ref "C18") (pin "2") (pinfunction "2_2") (pintype "passive"))
      (node (ref "U4") (pin "2") (pinfunction "VCC_2") (pintype "passive"))
    )
    (net (code "64") (name "Net-(U5-FB)") (class "Default")
      (node (ref "R23") (pin "1") (pinfunction "1_1") (pintype "passive"))
      (node (ref "R29") (pin "2") (pinfunction "2_2") (pintype "passive"))
      (node (ref "U5") (pin "5") (pinfunction "FB_5") (pintype "passive"))
    )
    (net (code "65") (name "Net-(U5-SW)") (class "Default")
      (node (ref "L3") (pin "1") (pinfunction "1_1") (pintype "passive"))
      (node (ref "U5") (pin "3") (pinfunction "SW_3") (pintype "passive"))
    )
    (net (code "66") (name "PGND") (class "Default")
      (node (ref "C10") (pin "1") (pinfunction "1_1") (pintype "passive"))
      (node (ref "C11") (pin "1") (pinfunction "1_1") (pintype "passive"))
      (node (ref "C12") (pin "1") (pinfunction "1_1") (pintype "passive"))
      (node (ref "C13") (pin "1") (pinfunction "1_1") (pintype "passive"))
      (node (ref "C14") (pin "1") (pinfunction "1_1") (pintype "passive"))
      (node (ref "C15") (pin "1") (pinfunction "1_1") (pintype "passive"))
      (node (ref "C16") (pin "1") (pinfunction "1_1") (pintype "passive"))
      (node (ref "C17") (pin "1") (pinfunction "1_1") (pintype "passive"))
      (node (ref "C18") (pin "1") (pinfunction "1_1") (pintype "passive"))
      (node (ref "C20") (pin "1") (pinfunction "1_1") (pintype "passive"))
      (node (ref "CN3") (pin "1") (pinfunction "-_1") (pintype "passive"))
      (node (ref "R16") (pin "2") (pinfunction "2_2") (pintype "passive"))
      (node (ref "R17") (pin "1") (pinfunction "1_1") (pintype "passive"))
      (node (ref "R25") (pin "1") (pinfunction "1_1") (pintype "passive"))
      (node (ref "R26") (pin "1") (pinfunction "1_1") (pintype "passive"))
      (node (ref "R27") (pin "1") (pinfunction "1_1") (pintype "passive"))
      (node (ref "R28") (pin "1") (pinfunction "1_1") (pintype "passive"))
      (node (ref "R29") (pin "1") (pinfunction "1_1") (pintype "passive"))
      (node (ref "U2") (pin "10") (pinfunction "SNA_10") (pintype "passive"))
      (node (ref "U2") (pin "11") (pinfunction "SNB_11") (pintype "passive"))
      (node (ref "U2") (pin "20") (pinfunction "SNC_20") (pintype "passive"))
      (node (ref "U2") (pin "40") (pinfunction "PGND_40") (pintype "passive"))
      (node (ref "U2") (pin "41") (pinfunction "EP_41") (pintype "passive"))
      (node (ref "U4") (pin "5") (pinfunction "GND_5") (pintype "passive"))
      (node (ref "U5") (pin "2") (pinfunction "GND_2") (pintype "passive"))
    )
    (net (code "67") (name "VCC") (class "Default")
      (node (ref "C10") (pin "2") (pinfunction "2_2") (pintype "passive"))
      (node (ref "C11") (pin "2") (pinfunction "2_2") (pintype "passive"))
      (node (ref "C12") (pin "2") (pinfunction "2_2") (pintype "passive"))
      (node (ref "C20") (pin "2") (pinfunction "2_2") (pintype "passive"))
      (node (ref "CN3") (pin "2") (pinfunction "+_2") (pintype "passive"))
      (node (ref "Q2") (pin "10") (pinfunction "D_10") (pintype "passive"))
      (node (ref "Q2") (pin "7") (pinfunction "D_7") (pintype "passive"))
      (node (ref "Q2") (pin "8") (pinfunction "D_8") (pintype "passive"))
      (node (ref "Q2") (pin "9") (pinfunction "D_9") (pintype "passive"))
      (node (ref "Q3") (pin "10") (pinfunction "D_10") (pintype "passive"))
      (node (ref "Q3") (pin "7") (pinfunction "D_7") (pintype "passive"))
      (node (ref "Q3") (pin "8") (pinfunction "D_8") (pintype "passive"))
      (node (ref "Q3") (pin "9") (pinfunction "D_9") (pintype "passive"))
      (node (ref "Q4") (pin "10") (pinfunction "D_10") (pintype "passive"))
      (node (ref "Q4") (pin "7") (pinfunction "D_7") (pintype "passive"))
      (node (ref "Q4") (pin "8") (pinfunction "D_8") (pintype "passive"))
      (node (ref "Q4") (pin "9") (pinfunction "D_9") (pintype "passive"))
      (node (ref "R21") (pin "1") (pinfunction "1_1") (pintype "passive"))
      (node (ref "R3") (pin "2") (pinfunction "2_2") (pintype "passive"))
      (node (ref "R6") (pin "2") (pinfunction "2_2") (pintype "passive"))
      (node (ref "U2") (pin "5") (pinfunction "VDRAIN_5") (pintype "passive"))
      (node (ref "U4") (pin "7") (pinfunction "IN_7") (pintype "passive"))
    )
    (net (code "68") (name "unconnected-(U1-VREF-Pad5)") (class "Default")
      (node (ref "U1") (pin "5") (pinfunction "VREF_5") (pintype "passive+no_connect"))
    )
    (net (code "69") (name "unconnected-(U3-PB6-Pad29)") (class "Default")
      (node (ref "U3") (pin "29") (pinfunction "PB6_29") (pintype "passive+no_connect"))
    )
    (net (code "70") (name "unconnected-(U3-PB7-Pad30)") (class "Default")
      (node (ref "U3") (pin "30") (pinfunction "PB7_30") (pintype "passive+no_connect"))
    )
    (net (code "71") (name "unconnected-(U3-PF1-OSC_OUT-Pad3)") (class "Default")
      (node (ref "U3") (pin "3") (pinfunction "PF1-OSC_OUT_3") (pintype "passive+no_connect"))
    )
    (net (code "72") (name "unconnected-(U4-PG-Pad8)") (class "Default")
      (node (ref "U4") (pin "8") (pinfunction "PG_8") (pintype "passive+no_connect"))
    )
  )
)
